# board.net
KiCad netlist of a schematic drawn in EAGLE
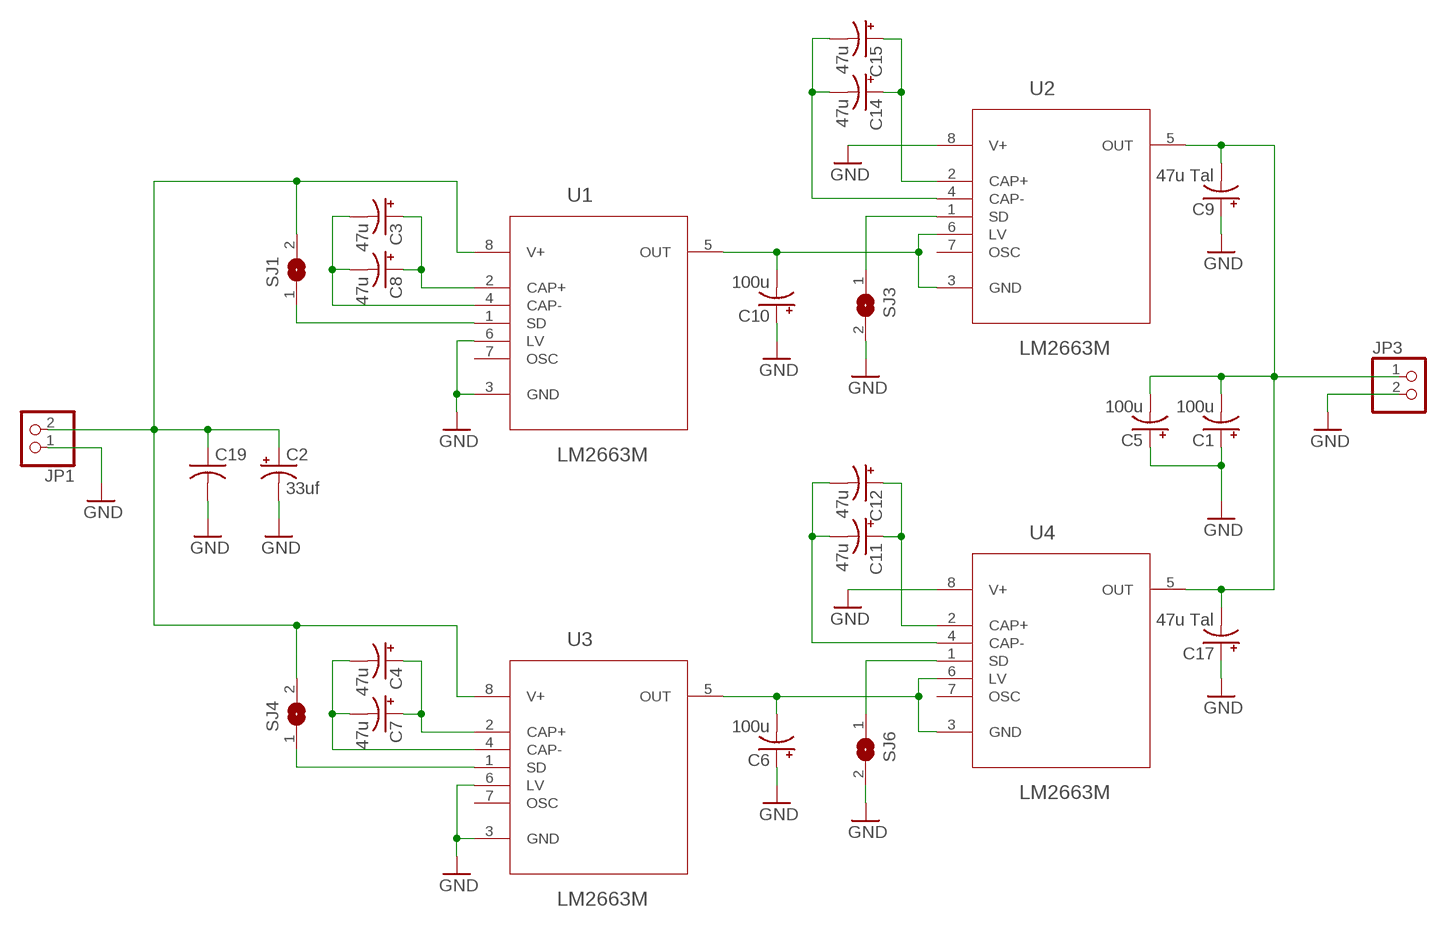
[diagram p0: schematic, sheet 1]

(export (version "E")
  (design (tool "Eeschema 10.0.6"))
  (components
    (comp (ref "C1")
      (value "100u")
      (footprint "eagle-import:E2,5-6")
      (libsource (lib "eagle-import") (part "CPOL-USE2.5-6"))
    )
    (comp (ref "C2")
      (value "33uf")
      (footprint "eagle-import:E2-5")
      (libsource (lib "eagle-import") (part "CPOL-USE2-5"))
    )
    (comp (ref "C3")
      (value "47u")
      (footprint "eagle-import:EIA3528-KIT")
      (libsource (lib "eagle-import") (part "CAP_POL3528-KIT"))
    )
    (comp (ref "C4")
      (value "47u")
      (footprint "eagle-import:EIA3528-KIT")
      (libsource (lib "eagle-import") (part "CAP_POL3528-KIT"))
    )
    (comp (ref "C5")
      (value "100u")
      (footprint "eagle-import:E2,5-6")
      (libsource (lib "eagle-import") (part "CPOL-USE2.5-6"))
    )
    (comp (ref "C6")
      (value "100u")
      (footprint "eagle-import:EIA7343")
      (libsource (lib "eagle-import") (part "CAP_POL7343"))
    )
    (comp (ref "C7")
      (value "47u")
      (footprint "eagle-import:EIA3528-KIT")
      (libsource (lib "eagle-import") (part "CAP_POL3528-KIT"))
    )
    (comp (ref "C8")
      (value "47u")
      (footprint "eagle-import:EIA3528-KIT")
      (libsource (lib "eagle-import") (part "CAP_POL3528-KIT"))
    )
    (comp (ref "C9")
      (value "47u Tal")
      (footprint "eagle-import:EIA6032")
      (libsource (lib "eagle-import") (part "CAP_POL6032"))
    )
    (comp (ref "C10")
      (value "100u")
      (footprint "eagle-import:EIA7343")
      (libsource (lib "eagle-import") (part "CAP_POL7343"))
    )
    (comp (ref "C11")
      (value "47u")
      (footprint "eagle-import:EIA3528-KIT")
      (libsource (lib "eagle-import") (part "CAP_POL3528-KIT"))
    )
    (comp (ref "C12")
      (value "47u")
      (footprint "eagle-import:EIA3528-KIT")
      (libsource (lib "eagle-import") (part "CAP_POL3528-KIT"))
    )
    (comp (ref "C14")
      (value "47u")
      (footprint "eagle-import:EIA3528-KIT")
      (libsource (lib "eagle-import") (part "CAP_POL3528-KIT"))
    )
    (comp (ref "C15")
      (value "47u")
      (footprint "eagle-import:EIA3528-KIT")
      (libsource (lib "eagle-import") (part "CAP_POL3528-KIT"))
    )
    (comp (ref "C17")
      (value "47u Tal")
      (footprint "eagle-import:EIA6032")
      (libsource (lib "eagle-import") (part "CAP_POL6032"))
    )
    (comp (ref "C19")
      (value "C-USC1206")
      (footprint "eagle-import:C1206")
      (libsource (lib "eagle-import") (part "C-USC1206"))
    )
    (comp (ref "JP1")
      (value "PINHD-1X2")
      (footprint "eagle-import:1X02")
      (libsource (lib "eagle-import") (part "PINHD-1X2"))
    )
    (comp (ref "JP3")
      (value "PINHD-1X2")
      (footprint "eagle-import:1X02")
      (libsource (lib "eagle-import") (part "PINHD-1X2"))
    )
    (comp (ref "SJ1") (value "SJ") (footprint "eagle-import:SJ") (libsource (lib "eagle-import") (part "SJ")))
    (comp (ref "SJ3") (value "SJ") (footprint "eagle-import:SJ") (libsource (lib "eagle-import") (part "SJ")))
    (comp (ref "SJ4") (value "SJ") (footprint "eagle-import:SJ") (libsource (lib "eagle-import") (part "SJ")))
    (comp (ref "SJ6") (value "SJ") (footprint "eagle-import:SJ") (libsource (lib "eagle-import") (part "SJ")))
    (comp (ref "U1")
      (value "LM2663M")
      (footprint "eagle-import:SOIC127P620X175-8N")
      (libsource (lib "eagle-import") (part "LM2663M"))
    )
    (comp (ref "U2")
      (value "LM2663M")
      (footprint "eagle-import:SOIC127P620X175-8N")
      (libsource (lib "eagle-import") (part "LM2663M"))
    )
    (comp (ref "U3")
      (value "LM2663M")
      (footprint "eagle-import:SOIC127P620X175-8N")
      (libsource (lib "eagle-import") (part "LM2663M"))
    )
    (comp (ref "U4")
      (value "LM2663M")
      (footprint "eagle-import:SOIC127P620X175-8N")
      (libsource (lib "eagle-import") (part "LM2663M"))
    )
  )
  (nets
    (net (code "1") (name "GND") (class "Default")
      (node (ref "C1") (pin "+") (pinfunction "+_+") (pintype "passive"))
      (node (ref "C10") (pin "A") (pinfunction "+_A") (pintype "passive"))
      (node (ref "C17") (pin "P$1") (pinfunction "+_P$1") (pintype "passive"))
      (node (ref "C19") (pin "2") (pinfunction "2_2") (pintype "passive"))
      (node (ref "C2") (pin "-") (pinfunction "-_-") (pintype "passive"))
      (node (ref "C5") (pin "+") (pinfunction "+_+") (pintype "passive"))
      (node (ref "C6") (pin "A") (pinfunction "+_A") (pintype "passive"))
      (node (ref "C9") (pin "P$1") (pinfunction "+_P$1") (pintype "passive"))
      (node (ref "JP1") (pin "1") (pinfunction "1_1") (pintype "passive"))
      (node (ref "JP3") (pin "2") (pinfunction "2_2") (pintype "passive"))
      (node (ref "SJ3") (pin "2") (pinfunction "2_2") (pintype "passive"))
      (node (ref "SJ6") (pin "2") (pinfunction "2_2") (pintype "passive"))
      (node (ref "U1") (pin "3") (pinfunction "GND_3") (pintype "passive"))
      (node (ref "U1") (pin "6") (pinfunction "LV_6") (pintype "input"))
      (node (ref "U2") (pin "8") (pinfunction "V+_8") (pintype "power_in"))
      (node (ref "U3") (pin "3") (pinfunction "GND_3") (pintype "passive"))
      (node (ref "U3") (pin "6") (pinfunction "LV_6") (pintype "input"))
      (node (ref "U4") (pin "8") (pinfunction "V+_8") (pintype "power_in"))
    )
    (net (code "2") (name "Net-(C3-+)") (class "Default")
      (node (ref "C3") (pin "A") (pinfunction "+_A") (pintype "passive"))
      (node (ref "C8") (pin "A") (pinfunction "+_A") (pintype "passive"))
      (node (ref "U1") (pin "2") (pinfunction "CAP+_2") (pintype "input"))
    )
    (net (code "3") (name "Net-(C3--)") (class "Default")
      (node (ref "C3") (pin "C") (pinfunction "-_C") (pintype "passive"))
      (node (ref "C8") (pin "C") (pinfunction "-_C") (pintype "passive"))
      (node (ref "U1") (pin "4") (pinfunction "CAP-_4") (pintype "input"))
    )
    (net (code "4") (name "Net-(C4-+)") (class "Default")
      (node (ref "C4") (pin "A") (pinfunction "+_A") (pintype "passive"))
      (node (ref "C7") (pin "A") (pinfunction "+_A") (pintype "passive"))
      (node (ref "U3") (pin "2") (pinfunction "CAP+_2") (pintype "input"))
    )
    (net (code "5") (name "Net-(C4--)") (class "Default")
      (node (ref "C4") (pin "C") (pinfunction "-_C") (pintype "passive"))
      (node (ref "C7") (pin "C") (pinfunction "-_C") (pintype "passive"))
      (node (ref "U3") (pin "4") (pinfunction "CAP-_4") (pintype "input"))
    )
    (net (code "6") (name "Net-(C6--)") (class "Default")
      (node (ref "C6") (pin "C") (pinfunction "-_C") (pintype "passive"))
      (node (ref "U3") (pin "5") (pinfunction "OUT_5") (pintype "output"))
      (node (ref "U4") (pin "3") (pinfunction "GND_3") (pintype "passive"))
      (node (ref "U4") (pin "6") (pinfunction "LV_6") (pintype "input"))
    )
    (net (code "7") (name "Net-(C10--)") (class "Default")
      (node (ref "C10") (pin "C") (pinfunction "-_C") (pintype "passive"))
      (node (ref "U1") (pin "5") (pinfunction "OUT_5") (pintype "output"))
      (node (ref "U2") (pin "3") (pinfunction "GND_3") (pintype "passive"))
      (node (ref "U2") (pin "6") (pinfunction "LV_6") (pintype "input"))
    )
    (net (code "8") (name "Net-(C11-+)") (class "Default")
      (node (ref "C11") (pin "A") (pinfunction "+_A") (pintype "passive"))
      (node (ref "C12") (pin "A") (pinfunction "+_A") (pintype "passive"))
      (node (ref "U4") (pin "2") (pinfunction "CAP+_2") (pintype "input"))
    )
    (net (code "9") (name "Net-(C11--)") (class "Default")
      (node (ref "C11") (pin "C") (pinfunction "-_C") (pintype "passive"))
      (node (ref "C12") (pin "C") (pinfunction "-_C") (pintype "passive"))
      (node (ref "U4") (pin "4") (pinfunction "CAP-_4") (pintype "input"))
    )
    (net (code "10") (name "Net-(C14-+)") (class "Default")
      (node (ref "C14") (pin "A") (pinfunction "+_A") (pintype "passive"))
      (node (ref "C15") (pin "A") (pinfunction "+_A") (pintype "passive"))
      (node (ref "U2") (pin "2") (pinfunction "CAP+_2") (pintype "input"))
    )
    (net (code "11") (name "Net-(C14--)") (class "Default")
      (node (ref "C14") (pin "C") (pinfunction "-_C") (pintype "passive"))
      (node (ref "C15") (pin "C") (pinfunction "-_C") (pintype "passive"))
      (node (ref "U2") (pin "4") (pinfunction "CAP-_4") (pintype "input"))
    )
    (net (code "12") (name "Net-(C17--)") (class "Default")
      (node (ref "C1") (pin "-") (pinfunction "-_-") (pintype "passive"))
      (node (ref "C17") (pin "P$2") (pinfunction "-_P$2") (pintype "passive"))
      (node (ref "C5") (pin "-") (pinfunction "-_-") (pintype "passive"))
      (node (ref "C9") (pin "P$2") (pinfunction "-_P$2") (pintype "passive"))
      (node (ref "JP3") (pin "1") (pinfunction "1_1") (pintype "passive"))
      (node (ref "U2") (pin "5") (pinfunction "OUT_5") (pintype "output"))
      (node (ref "U4") (pin "5") (pinfunction "OUT_5") (pintype "output"))
    )
    (net (code "13") (name "Net-(U1-SD)") (class "Default")
      (node (ref "SJ1") (pin "1") (pinfunction "1_1") (pintype "passive"))
      (node (ref "U1") (pin "1") (pinfunction "SD_1") (pintype "input"))
    )
    (net (code "14") (name "Net-(U1-V+)") (class "Default")
      (node (ref "C19") (pin "1") (pinfunction "1_1") (pintype "passive"))
      (node (ref "C2") (pin "+") (pinfunction "+_+") (pintype "passive"))
      (node (ref "JP1") (pin "2") (pinfunction "2_2") (pintype "passive"))
      (node (ref "SJ1") (pin "2") (pinfunction "2_2") (pintype "passive"))
      (node (ref "SJ4") (pin "2") (pinfunction "2_2") (pintype "passive"))
      (node (ref "U1") (pin "8") (pinfunction "V+_8") (pintype "power_in"))
      (node (ref "U3") (pin "8") (pinfunction "V+_8") (pintype "power_in"))
    )
    (net (code "15") (name "Net-(U2-SD)") (class "Default")
      (node (ref "SJ3") (pin "1") (pinfunction "1_1") (pintype "passive"))
      (node (ref "U2") (pin "1") (pinfunction "SD_1") (pintype "input"))
    )
    (net (code "16") (name "Net-(U3-SD)") (class "Default")
      (node (ref "SJ4") (pin "1") (pinfunction "1_1") (pintype "passive"))
      (node (ref "U3") (pin "1") (pinfunction "SD_1") (pintype "input"))
    )
    (net (code "17") (name "Net-(U4-SD)") (class "Default")
      (node (ref "SJ6") (pin "1") (pinfunction "1_1") (pintype "passive"))
      (node (ref "U4") (pin "1") (pinfunction "SD_1") (pintype "input"))
    )
    (net (code "18") (name "unconnected-(U1-OSC-Pad7)") (class "Default")
      (node (ref "U1") (pin "7") (pinfunction "OSC_7") (pintype "input"))
    )
    (net (code "19") (name "unconnected-(U2-OSC-Pad7)") (class "Default")
      (node (ref "U2") (pin "7") (pinfunction "OSC_7") (pintype "input"))
    )
    (net (code "20") (name "unconnected-(U3-OSC-Pad7)") (class "Default")
      (node (ref "U3") (pin "7") (pinfunction "OSC_7") (pintype "input"))
    )
    (net (code "21") (name "unconnected-(U4-OSC-Pad7)") (class "Default")
      (node (ref "U4") (pin "7") (pinfunction "OSC_7") (pintype "input"))
    )
  )
)
